# SpectrumCtrl.net
KiCad netlist of a schematic drawn in EAGLE
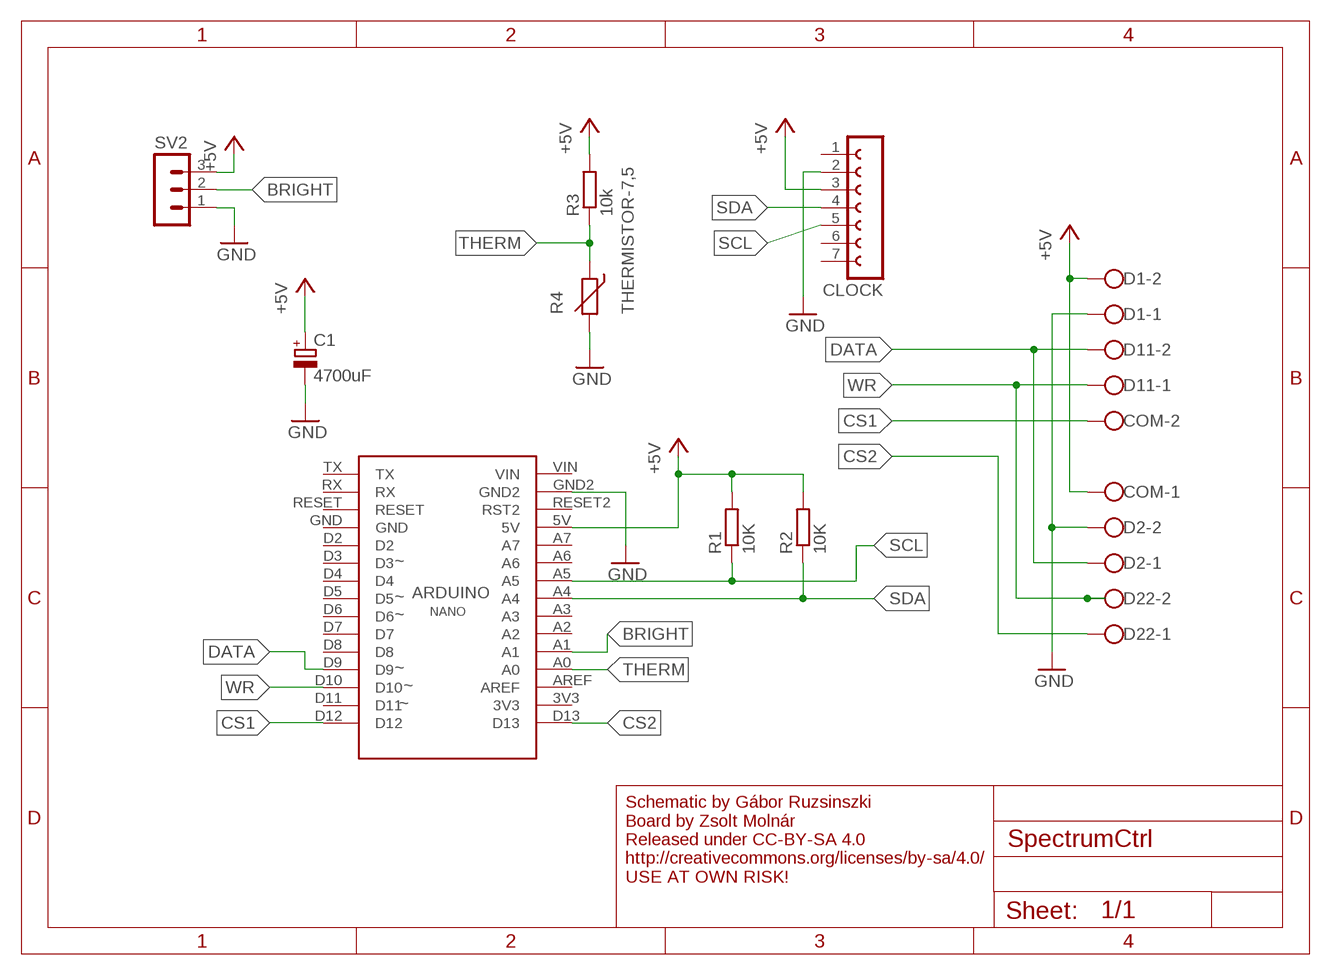
[diagram p0: schematic, sheet 1]

(export (version "E")
  (design (tool "Eeschema 10.0.6"))
  (components
    (comp (ref "C1")
      (value "4700uF")
      (footprint "eagle-import:E7,5-16")
      (libsource (lib "eagle-import") (part "CPOL-EUE7.5-16"))
    )
    (comp (ref "CLOCK")
      (value "FE07-1")
      (footprint "eagle-import:FE07")
      (libsource (lib "eagle-import") (part "FE07-1"))
    )
    (comp (ref "COM")
      (value "W237-102")
      (footprint "eagle-import:W237-102")
      (fields (field (name "MPN") "237-102"))
      (libsource (lib "eagle-import") (part "W237-102"))
    )
    (comp (ref "D1")
      (value "W237-102")
      (footprint "eagle-import:W237-102")
      (fields (field (name "MPN") "237-102"))
      (libsource (lib "eagle-import") (part "W237-102"))
    )
    (comp (ref "D2")
      (value "W237-102")
      (footprint "eagle-import:W237-102")
      (fields (field (name "MPN") "237-102"))
      (libsource (lib "eagle-import") (part "W237-102"))
    )
    (comp (ref "D11")
      (value "W237-102")
      (footprint "eagle-import:W237-102")
      (fields (field (name "MPN") "237-102"))
      (libsource (lib "eagle-import") (part "W237-102"))
    )
    (comp (ref "D22")
      (value "W237-102")
      (footprint "eagle-import:W237-102")
      (fields (field (name "MPN") "237-102"))
      (libsource (lib "eagle-import") (part "W237-102"))
    )
    (comp (ref "R1")
      (value "10K")
      (footprint "eagle-import:0309_12")
      (libsource (lib "eagle-import") (part "R-EU_0309/12"))
    )
    (comp (ref "R2")
      (value "10K")
      (footprint "eagle-import:0309_12")
      (libsource (lib "eagle-import") (part "R-EU_0309/12"))
    )
    (comp (ref "R3")
      (value "10k")
      (footprint "eagle-import:0309_12")
      (libsource (lib "eagle-import") (part "R-EU_0309/12"))
    )
    (comp (ref "R4")
      (value "THERMISTOR-7,5")
      (footprint "eagle-import:R-7,5")
      (libsource (lib "eagle-import") (part "THERMISTOR-7,5"))
    )
    (comp (ref "SV2")
      (value "MA03-1")
      (footprint "eagle-import:MA03-1")
      (libsource (lib "eagle-import") (part "MA03-1"))
    )
    (comp (ref "U$1")
      (value "NANO")
      (footprint "eagle-import:NANO")
      (libsource (lib "eagle-import") (part "NANO"))
    )
  )
  (nets
    (net (code "1") (name "+5V") (class "Default")
      (node (ref "C1") (pin "+") (pinfunction "+_+") (pintype "passive"))
      (node (ref "CLOCK") (pin "3") (pinfunction "3_3") (pintype "passive"))
      (node (ref "COM") (pin "1") (pinfunction "KL_1") (pintype "passive"))
      (node (ref "D1") (pin "2") (pinfunction "KL_2") (pintype "passive"))
      (node (ref "R1") (pin "2") (pinfunction "2_2") (pintype "passive"))
      (node (ref "R2") (pin "2") (pinfunction "2_2") (pintype "passive"))
      (node (ref "R3") (pin "2") (pinfunction "2_2") (pintype "passive"))
      (node (ref "SV2") (pin "3") (pinfunction "3_3") (pintype "passive"))
      (node (ref "U$1") (pin "5V") (pinfunction "5V_5V") (pintype "bidirectional"))
    )
    (net (code "2") (name "BRIGHT") (class "Default")
      (node (ref "SV2") (pin "2") (pinfunction "2_2") (pintype "passive"))
      (node (ref "U$1") (pin "A1") (pinfunction "A1_A1") (pintype "bidirectional"))
    )
    (net (code "3") (name "CS1") (class "Default")
      (node (ref "COM") (pin "2") (pinfunction "KL_2") (pintype "passive"))
      (node (ref "U$1") (pin "D12") (pinfunction "D12_D12") (pintype "bidirectional"))
    )
    (net (code "4") (name "CS2") (class "Default")
      (node (ref "D22") (pin "1") (pinfunction "KL_1") (pintype "passive"))
      (node (ref "U$1") (pin "D13") (pinfunction "D13_D13") (pintype "bidirectional"))
    )
    (net (code "5") (name "DATA") (class "Default")
      (node (ref "D11") (pin "2") (pinfunction "KL_2") (pintype "passive"))
      (node (ref "D2") (pin "1") (pinfunction "KL_1") (pintype "passive"))
      (node (ref "U$1") (pin "D9") (pinfunction "D9_D9") (pintype "bidirectional"))
    )
    (net (code "6") (name "GND") (class "Default")
      (node (ref "C1") (pin "-") (pinfunction "-_-") (pintype "passive"))
      (node (ref "CLOCK") (pin "2") (pinfunction "2_2") (pintype "passive"))
      (node (ref "D1") (pin "1") (pinfunction "KL_1") (pintype "passive"))
      (node (ref "D2") (pin "2") (pinfunction "KL_2") (pintype "passive"))
      (node (ref "R4") (pin "2") (pinfunction "2_2") (pintype "passive"))
      (node (ref "SV2") (pin "1") (pinfunction "1_1") (pintype "passive"))
      (node (ref "U$1") (pin "GND2") (pinfunction "GND2_GND2") (pintype "bidirectional"))
    )
    (net (code "7") (name "SCL") (class "Default")
      (node (ref "CLOCK") (pin "5") (pinfunction "5_5") (pintype "passive"))
      (node (ref "R1") (pin "1") (pinfunction "1_1") (pintype "passive"))
      (node (ref "U$1") (pin "A5") (pinfunction "A5_A5") (pintype "bidirectional"))
    )
    (net (code "8") (name "SDA") (class "Default")
      (node (ref "CLOCK") (pin "4") (pinfunction "4_4") (pintype "passive"))
      (node (ref "R2") (pin "1") (pinfunction "1_1") (pintype "passive"))
      (node (ref "U$1") (pin "A4") (pinfunction "A4_A4") (pintype "bidirectional"))
    )
    (net (code "9") (name "THERM") (class "Default")
      (node (ref "R3") (pin "1") (pinfunction "1_1") (pintype "passive"))
      (node (ref "R4") (pin "1") (pinfunction "1_1") (pintype "passive"))
      (node (ref "U$1") (pin "A0") (pinfunction "A0_A0") (pintype "bidirectional"))
    )
    (net (code "10") (name "WR") (class "Default")
      (node (ref "D11") (pin "1") (pinfunction "KL_1") (pintype "passive"))
      (node (ref "D22") (pin "2") (pinfunction "KL_2") (pintype "passive"))
      (node (ref "U$1") (pin "D10") (pinfunction "D10_D10") (pintype "bidirectional"))
    )
    (net (code "11") (name "unconnected-(CLOCK-Pad1)") (class "Default")
      (node (ref "CLOCK") (pin "1") (pinfunction "1_1") (pintype "passive"))
    )
    (net (code "12") (name "unconnected-(CLOCK-Pad6)") (class "Default")
      (node (ref "CLOCK") (pin "6") (pinfunction "6_6") (pintype "passive"))
    )
    (net (code "13") (name "unconnected-(CLOCK-Pad7)") (class "Default")
      (node (ref "CLOCK") (pin "7") (pinfunction "7_7") (pintype "passive"))
    )
    (net (code "14") (name "unconnected-(U$1-Pad3V3)") (class "Default")
      (node (ref "U$1") (pin "3V3") (pinfunction "3V3_3V3") (pintype "bidirectional"))
    )
    (net (code "15") (name "unconnected-(U$1-PadA2)") (class "Default")
      (node (ref "U$1") (pin "A2") (pinfunction "A2_A2") (pintype "bidirectional"))
    )
    (net (code "16") (name "unconnected-(U$1-PadA3)") (class "Default")
      (node (ref "U$1") (pin "A3") (pinfunction "A3_A3") (pintype "bidirectional"))
    )
    (net (code "17") (name "unconnected-(U$1-PadA6)") (class "Default")
      (node (ref "U$1") (pin "A6") (pinfunction "A6_A6") (pintype "bidirectional"))
    )
    (net (code "18") (name "unconnected-(U$1-PadA7)") (class "Default")
      (node (ref "U$1") (pin "A7") (pinfunction "A7_A7") (pintype "bidirectional"))
    )
    (net (code "19") (name "unconnected-(U$1-PadAREF)") (class "Default")
      (node (ref "U$1") (pin "AREF") (pinfunction "AREF_AREF") (pintype "bidirectional"))
    )
    (net (code "20") (name "unconnected-(U$1-PadD2)") (class "Default")
      (node (ref "U$1") (pin "D2") (pinfunction "D2_D2") (pintype "bidirectional"))
    )
    (net (code "21") (name "unconnected-(U$1-PadD3)") (class "Default")
      (node (ref "U$1") (pin "D3") (pinfunction "D3_D3") (pintype "bidirectional"))
    )
    (net (code "22") (name "unconnected-(U$1-PadD4)") (class "Default")
      (node (ref "U$1") (pin "D4") (pinfunction "D4_D4") (pintype "bidirectional"))
    )
    (net (code "23") (name "unconnected-(U$1-PadD5)") (class "Default")
      (node (ref "U$1") (pin "D5") (pinfunction "D5_D5") (pintype "bidirectional"))
    )
    (net (code "24") (name "unconnected-(U$1-PadD6)") (class "Default")
      (node (ref "U$1") (pin "D6") (pinfunction "D6_D6") (pintype "bidirectional"))
    )
    (net (code "25") (name "unconnected-(U$1-PadD7)") (class "Default")
      (node (ref "U$1") (pin "D7") (pinfunction "D7_D7") (pintype "bidirectional"))
    )
    (net (code "26") (name "unconnected-(U$1-PadD8)") (class "Default")
      (node (ref "U$1") (pin "D8") (pinfunction "D8_D8") (pintype "bidirectional"))
    )
    (net (code "27") (name "unconnected-(U$1-PadD11)") (class "Default")
      (node (ref "U$1") (pin "D11") (pinfunction "D11_D11") (pintype "bidirectional"))
    )
    (net (code "28") (name "unconnected-(U$1-PadGND)") (class "Default")
      (node (ref "U$1") (pin "GND") (pinfunction "GND_GND") (pintype "bidirectional"))
    )
    (net (code "29") (name "unconnected-(U$1-PadRESET)") (class "Default")
      (node (ref "U$1") (pin "RESET") (pinfunction "RESET_RESET") (pintype "bidirectional"))
    )
    (net (code "30") (name "unconnected-(U$1-PadRX)") (class "Default")
      (node (ref "U$1") (pin "RX") (pinfunction "RX_RX") (pintype "bidirectional"))
    )
    (net (code "31") (name "unconnected-(U$1-PadTX)") (class "Default")
      (node (ref "U$1") (pin "TX") (pinfunction "TX_TX") (pintype "bidirectional"))
    )
    (net (code "32") (name "unconnected-(U$1-PadVIN)") (class "Default")
      (node (ref "U$1") (pin "VIN") (pinfunction "VIN_VIN") (pintype "bidirectional"))
    )
    (net (code "33") (name "unconnected-(U$1-RST2-PadRESET2)") (class "Default")
      (node (ref "U$1") (pin "RESET2") (pinfunction "RST2_RESET2") (pintype "bidirectional"))
    )
  )
)
